# X2X.net
KiCad netlist of a schematic drawn in Altium Designer
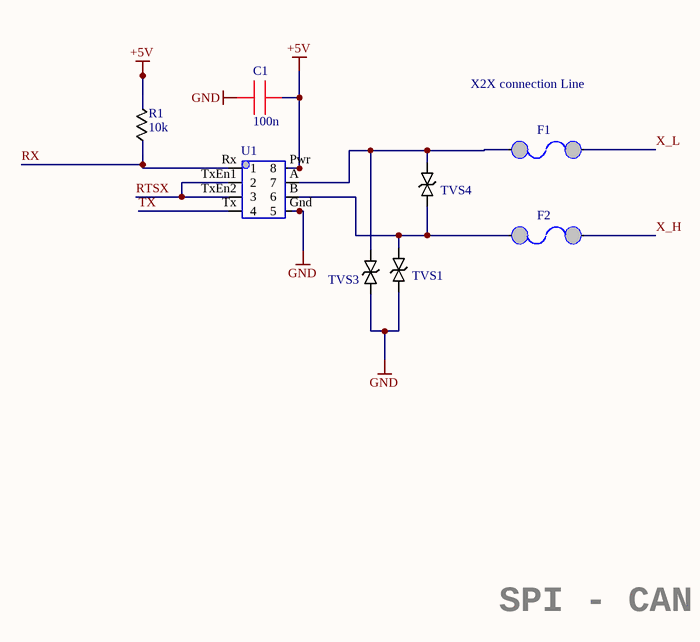
[diagram p0: X2X.SchDoc]

(export (version "E")
  (design (tool "Eeschema 10.0.6"))
  (components
    (comp (ref "C1")
      (value "100n")
      (footprint "0603 - Cap")
      (fields (field (name "PART NUMBER") "CC0603KRX7R9BB104"))
      (libsource (lib "kontr") (part "0805 Cap"))
    )
    (comp (ref "F1")
      (value "Fuse PTS")
      (footprint "1210_MF")
      (fields (field (name "PART NUMBER") "MF-USMF005-2"))
      (libsource (lib "kontr") (part "Fuse PTS"))
    )
    (comp (ref "F2")
      (value "Fuse PTS")
      (footprint "1210_MF")
      (fields (field (name "PART NUMBER") "MF-USMF005-2"))
      (libsource (lib "kontr") (part "Fuse PTS"))
    )
    (comp (ref "R1")
      (value "10k")
      (footprint "0603_Res")
      (description "RC0603JR-0710K")
      (fields (field (name "PART NUMBER") "RC0603FR-0710KL"))
      (libsource (lib "kontr") (part "Resistor 0805"))
    )
    (comp (ref "TVS1")
      (value "~")
      (footprint "DO-214AC")
      (fields (field (name "PART NUMBER") "SMAJ5.0CA"))
      (libsource (lib "kontr") (part "SMAJ5.0CA"))
    )
    (comp (ref "TVS3")
      (value "~")
      (footprint "DO-214AC")
      (fields (field (name "PART NUMBER") "SMAJ5.0CA"))
      (libsource (lib "kontr") (part "SMAJ5.0CA"))
    )
    (comp (ref "TVS4")
      (value "~")
      (footprint "DO-214AC")
      (fields (field (name "PART NUMBER") "SMAJ5.0CA"))
      (libsource (lib "kontr") (part "SMAJ5.0CA"))
    )
    (comp (ref "U1")
      (value "~")
      (footprint "MAX485 - duplicate")
      (fields (field (name "PART NUMBER") "SN65HVD3082EDR"))
      (libsource (lib "Schlib1") (part "MAX485"))
    )
  )
  (nets
    (net (code "1") (name "+5V") (class "Default")
      (node (ref "C1") (pin "1") (pinfunction "1_1") (pintype "passive"))
      (node (ref "R1") (pin "2") (pintype "passive"))
      (node (ref "U1") (pin "Pwr") (pinfunction "8_Pwr") (pintype "passive"))
    )
    (net (code "2") (name "/RTSX") (class "Default")
      (node (ref "U1") (pin "TxEn1") (pinfunction "2_TxEn1") (pintype "passive"))
      (node (ref "U1") (pin "TxEn2") (pinfunction "3_TxEn2") (pintype "passive"))
    )
    (net (code "3") (name "/RX") (class "Default")
      (node (ref "R1") (pin "1") (pintype "passive"))
      (node (ref "U1") (pin "Rx") (pinfunction "1_Rx") (pintype "passive"))
    )
    (net (code "4") (name "/TX") (class "Default")
      (node (ref "U1") (pin "Tx") (pinfunction "4_Tx") (pintype "passive"))
    )
    (net (code "5") (name "/X_H") (class "Default")
      (node (ref "F2") (pin "1") (pinfunction "1_1") (pintype "passive"))
    )
    (net (code "6") (name "/X_L") (class "Default")
      (node (ref "F1") (pin "1") (pinfunction "1_1") (pintype "passive"))
    )
    (net (code "7") (name "GND") (class "Default")
      (node (ref "C1") (pin "2") (pinfunction "2_2") (pintype "passive"))
      (node (ref "TVS1") (pin "1") (pinfunction "1_1") (pintype "passive"))
      (node (ref "TVS3") (pin "1") (pinfunction "1_1") (pintype "passive"))
      (node (ref "U1") (pin "Gnd") (pinfunction "5_Gnd") (pintype "passive"))
    )
    (net (code "8") (name "Net-(U1-6)") (class "Default")
      (node (ref "F2") (pin "2") (pinfunction "2_2") (pintype "passive"))
      (node (ref "TVS1") (pin "2") (pinfunction "2_2") (pintype "passive"))
      (node (ref "TVS4") (pin "1") (pinfunction "1_1") (pintype "passive"))
      (node (ref "U1") (pin "B") (pinfunction "6_B") (pintype "passive"))
    )
    (net (code "9") (name "Net-(U1-7)") (class "Default")
      (node (ref "F1") (pin "2") (pinfunction "2_2") (pintype "passive"))
      (node (ref "TVS3") (pin "2") (pinfunction "2_2") (pintype "passive"))
      (node (ref "TVS4") (pin "2") (pinfunction "2_2") (pintype "passive"))
      (node (ref "U1") (pin "A") (pinfunction "7_A") (pintype "passive"))
    )
  )
)
